# BSB-LAN-Full-Wifi.net
KiCad netlist of a schematic drawn in EAGLE
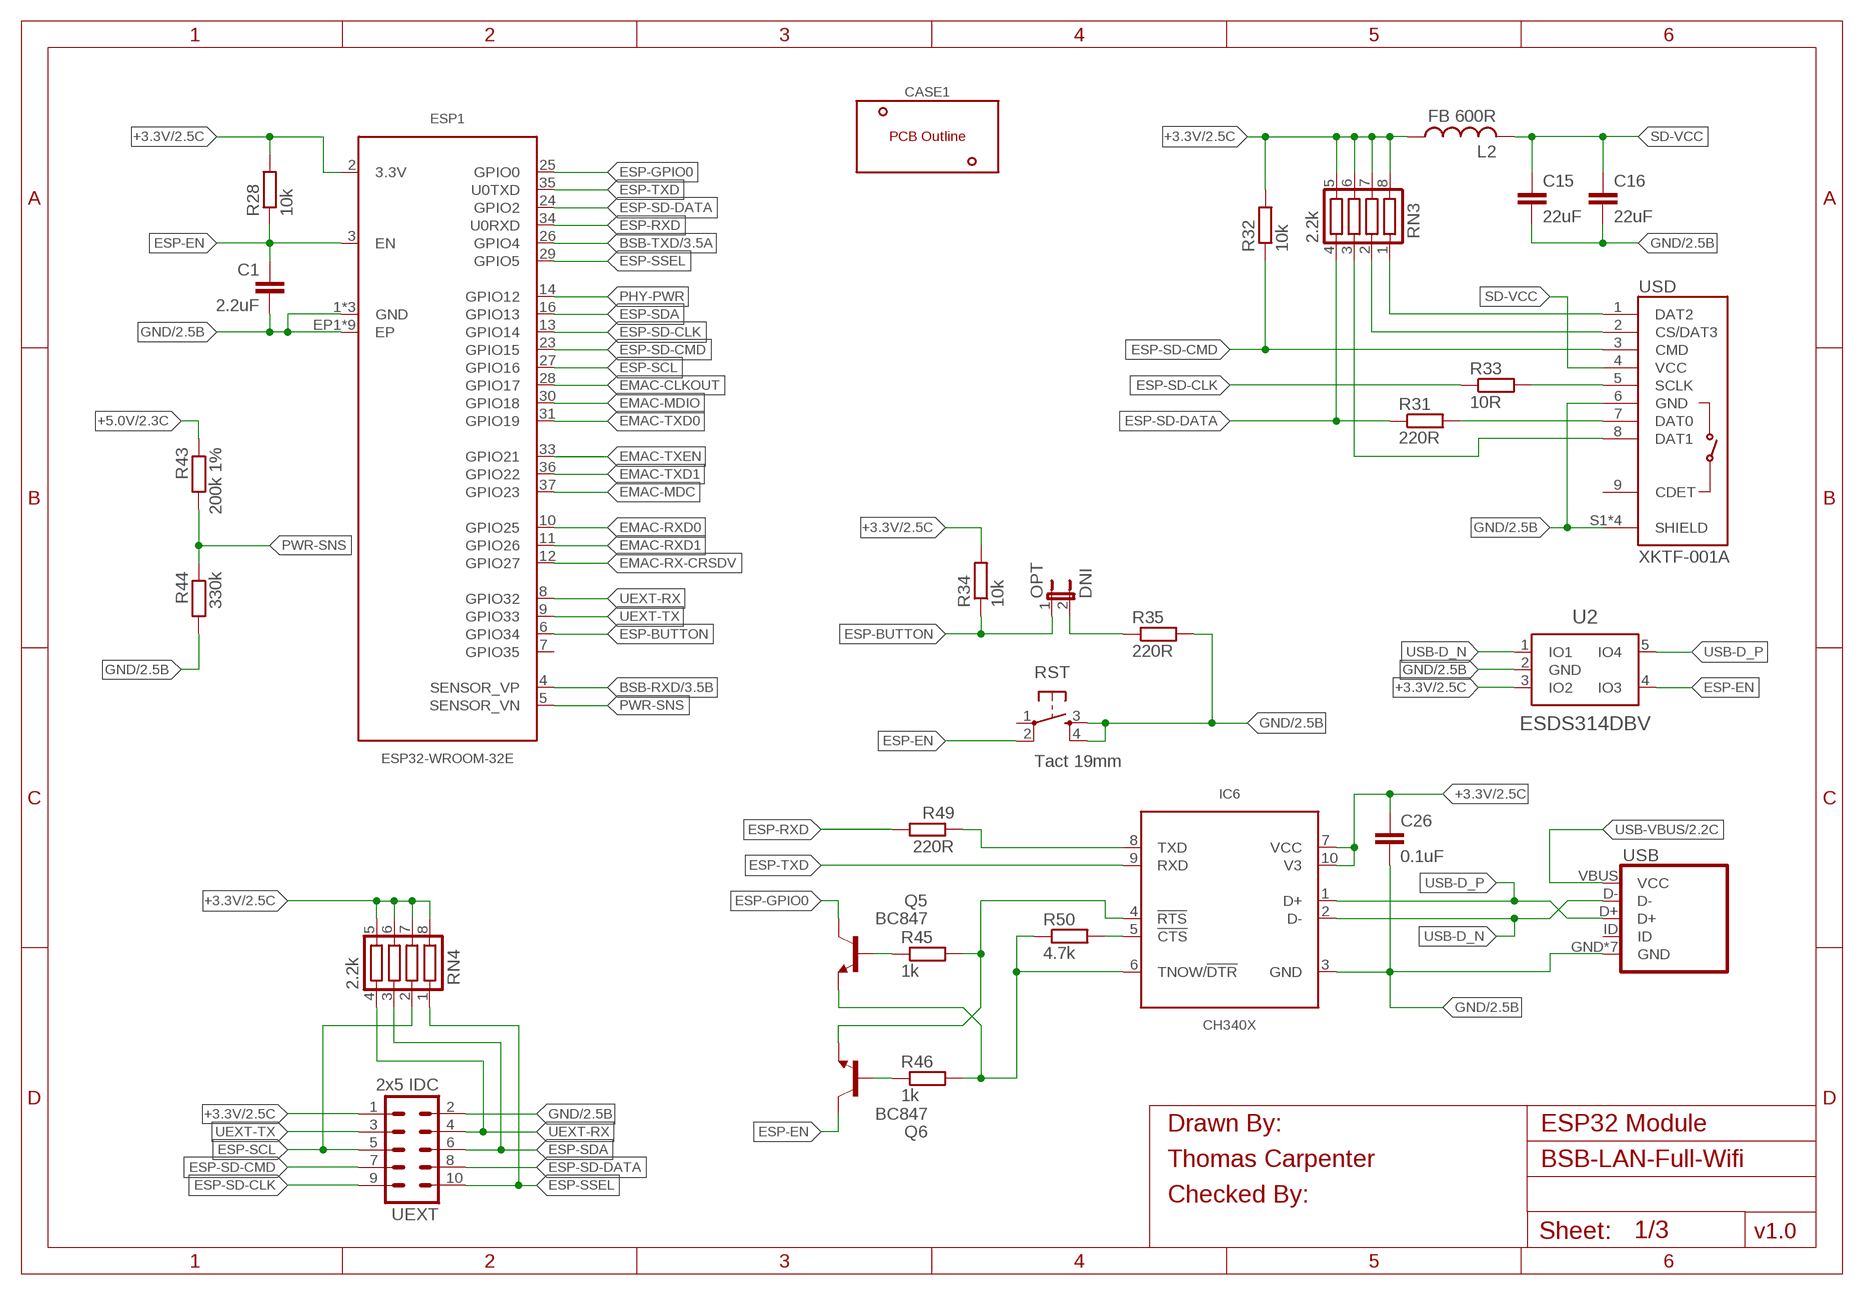
[diagram p0: schematic, sheet 1]
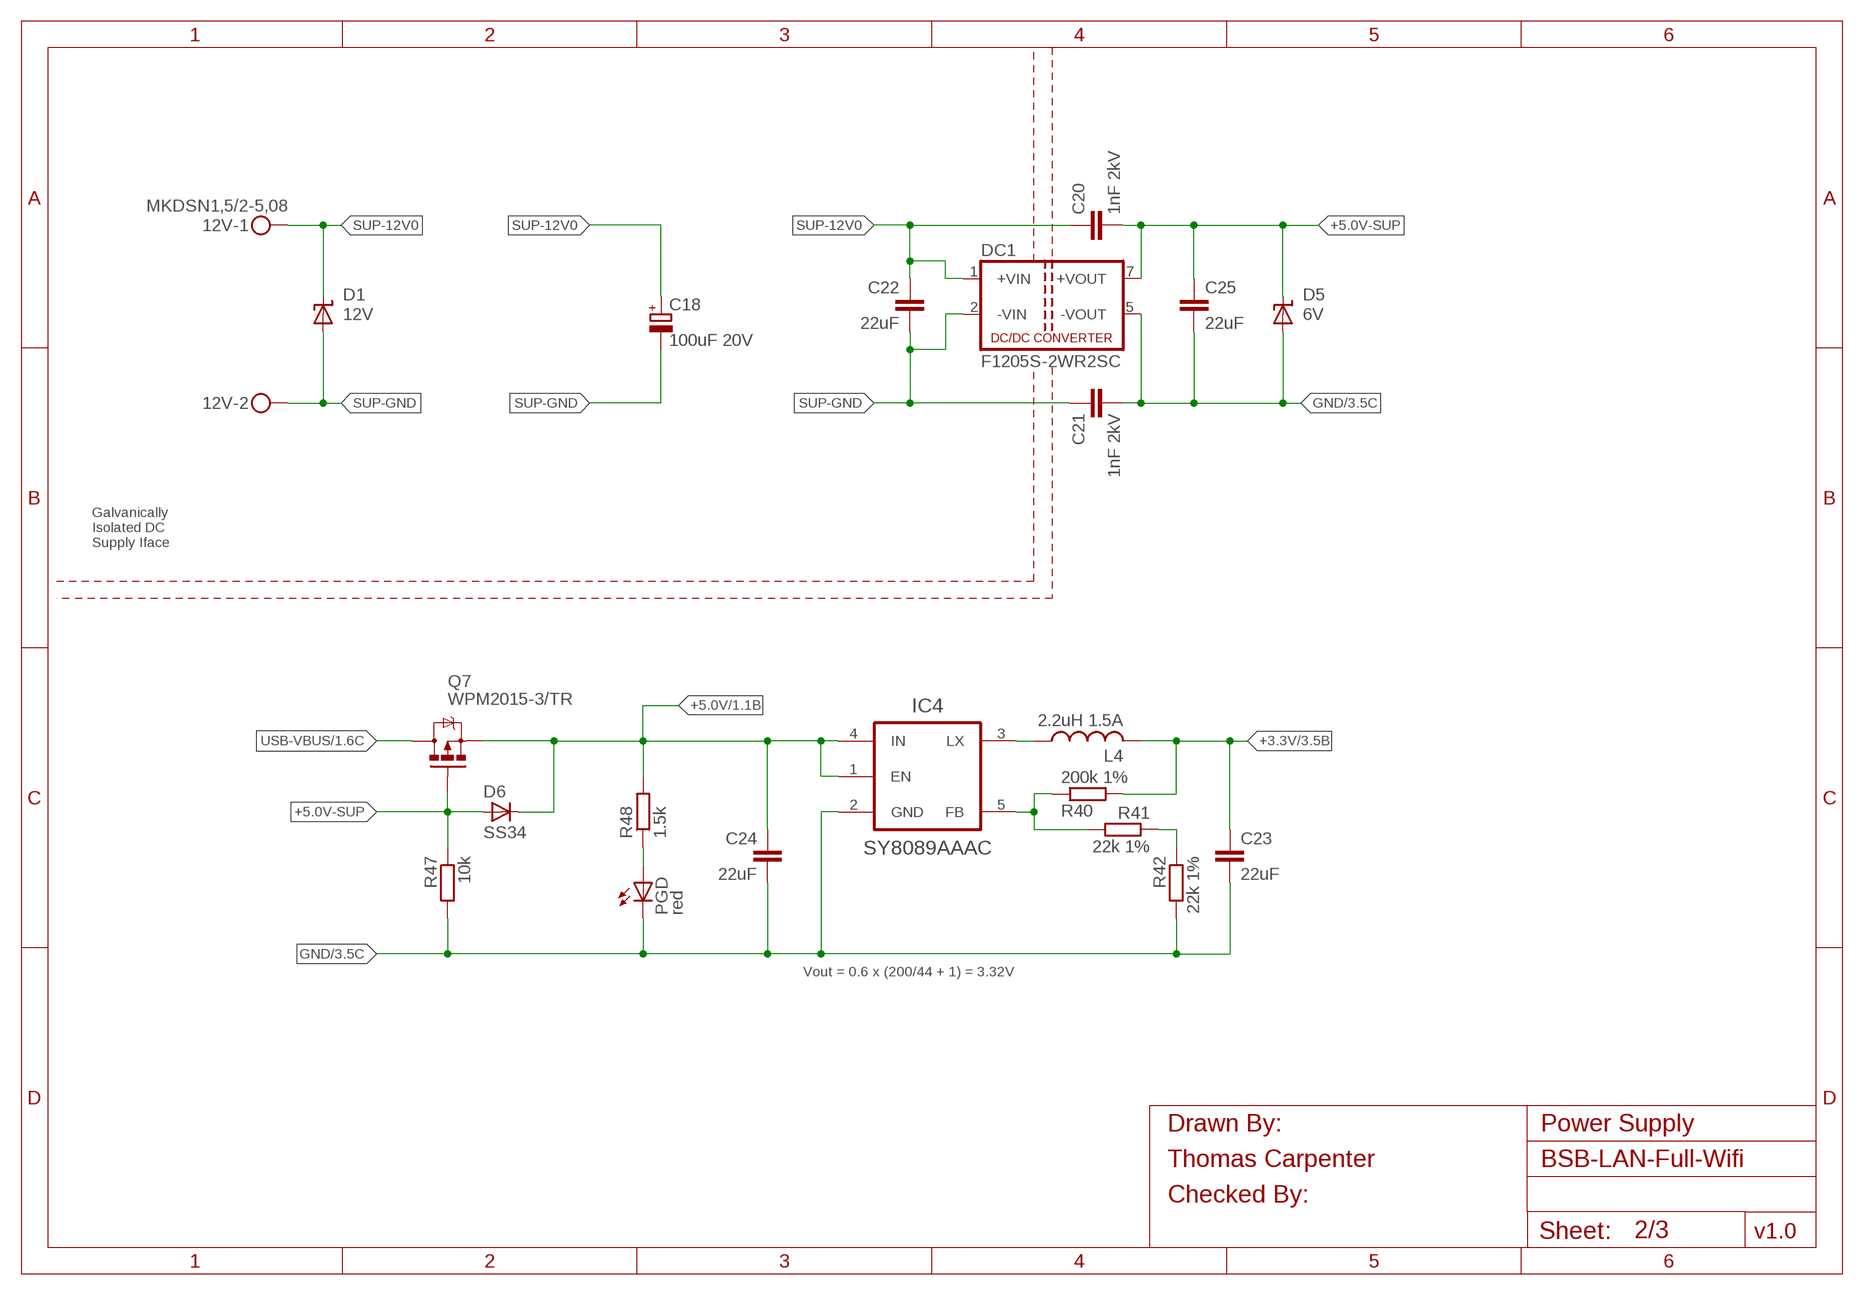
[diagram p1: schematic, sheet 2]
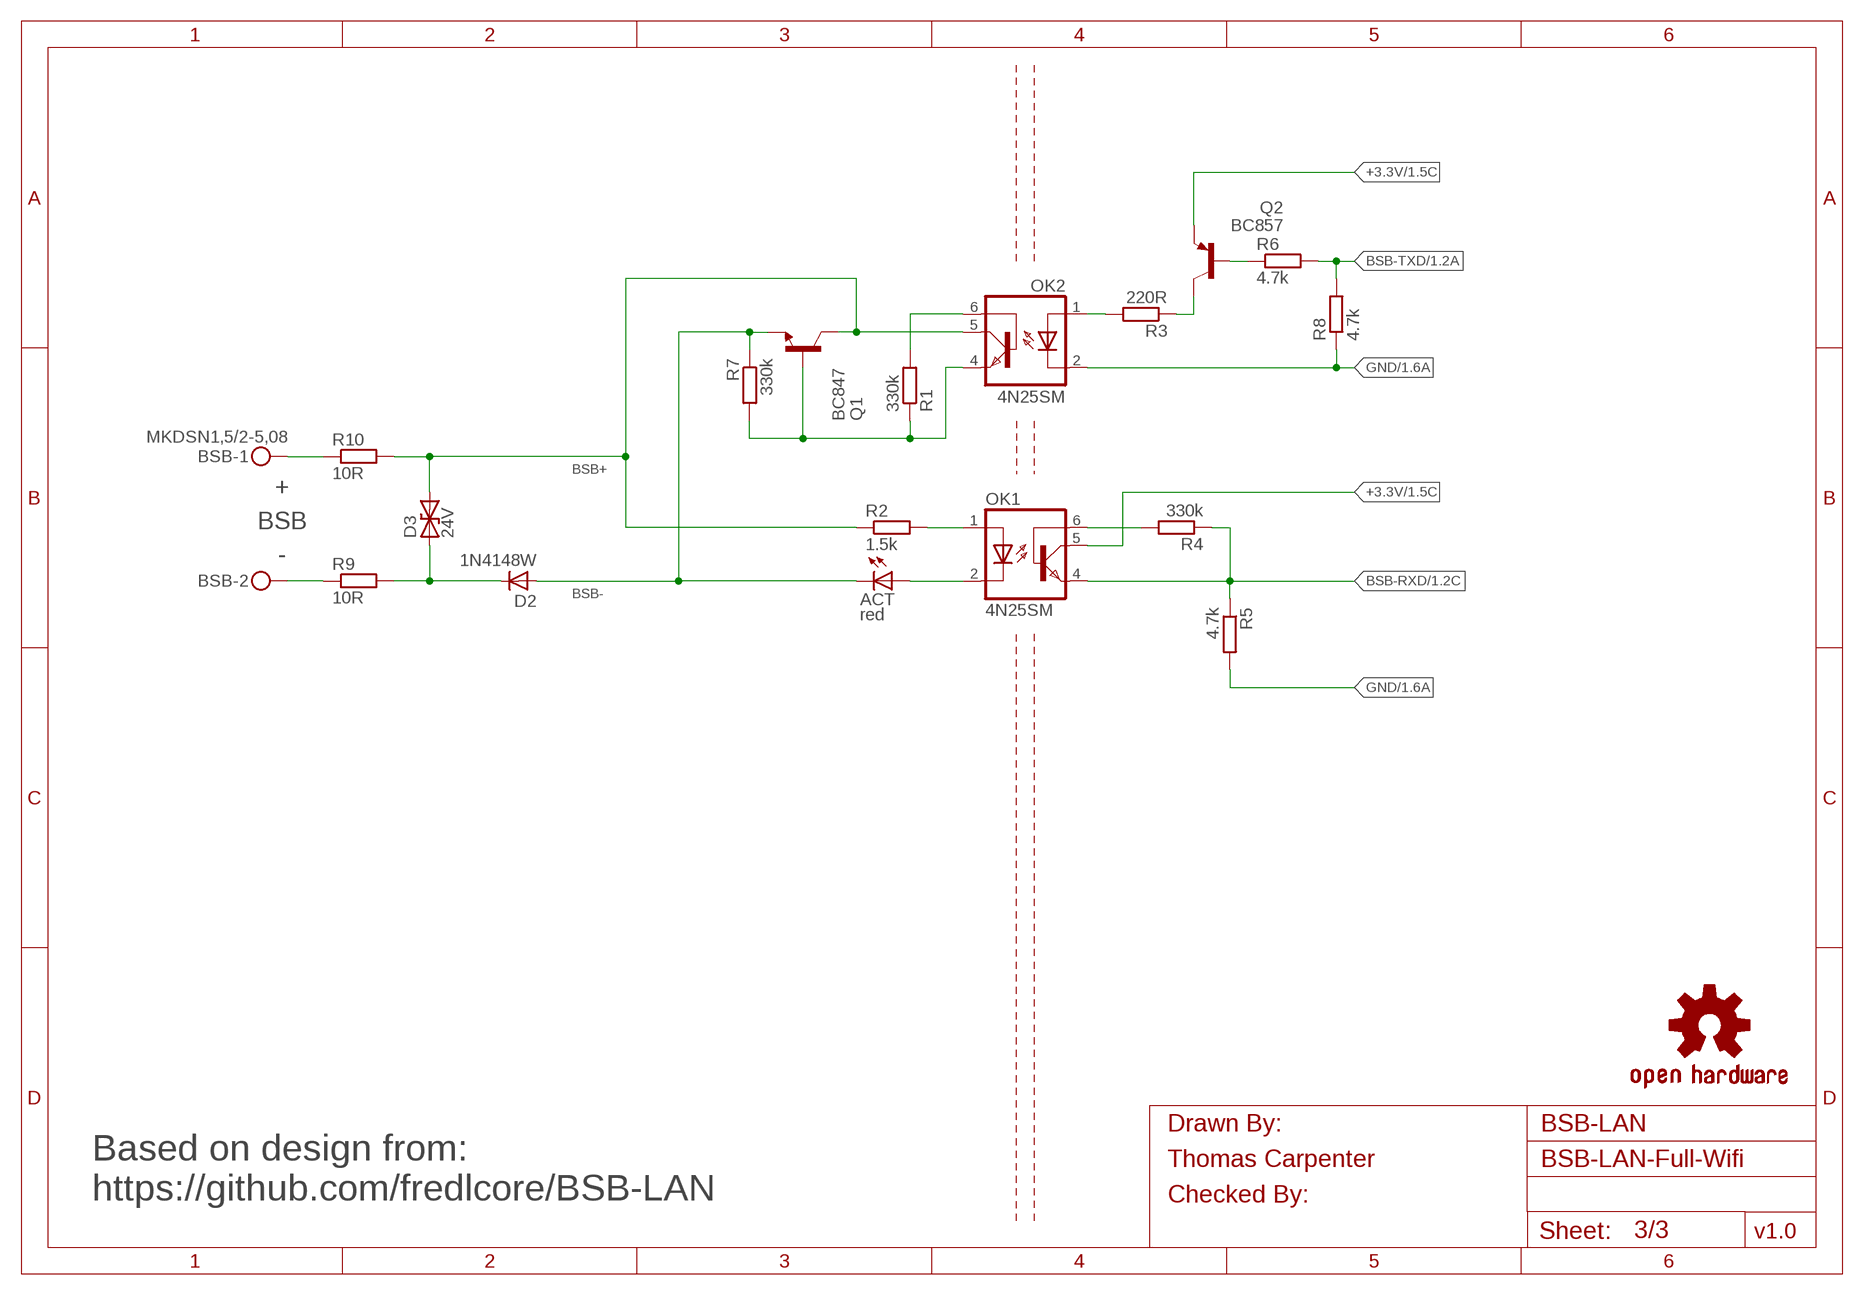
[diagram p2: schematic, sheet 3]

(export (version "E")
  (design (tool "Eeschema 10.0.6"))
  (components
    (comp (ref "12V")
      (value "MKDSN1,5/2-5,08")
      (footprint "eagle-import:MKDSN1_5-2-5_08")
      (fields (field (name "LCSC_PART") "C5183989"))
      (libsource (lib "eagle-import") (part "MKDSN1,5/2-5,08"))
    )
    (comp (ref "C18")
      (value "100uF 20V")
      (footprint "eagle-import:SMC_D")
      (fields (field (name "LCSC_PART") "C7224"))
      (libsource (lib "eagle-import") (part "CPOL-EUSMCD"))
    )
    (comp (ref "C20")
      (value "1nF 2kV")
      (footprint "eagle-import:C1206L")
      (fields (field (name "LCSC_PART") "C9196"))
      (libsource (lib "eagle-import") (part "C-EUC1206L"))
    )
    (comp (ref "C21")
      (value "1nF 2kV")
      (footprint "eagle-import:C1206L")
      (fields (field (name "LCSC_PART") "C9196"))
      (libsource (lib "eagle-import") (part "C-EUC1206L"))
    )
    (comp (ref "C22")
      (value "22uF")
      (footprint "eagle-import:C0805")
      (fields (field (name "LCSC_PART") "C45783"))
      (libsource (lib "eagle-import") (part "C-EUC0805"))
    )
    (comp (ref "C23")
      (value "22uF")
      (footprint "eagle-import:C0805")
      (fields (field (name "LCSC_PART") "C45783"))
      (libsource (lib "eagle-import") (part "C-EUC0805"))
    )
    (comp (ref "C24")
      (value "22uF")
      (footprint "eagle-import:C0805")
      (fields (field (name "LCSC_PART") "C45783"))
      (libsource (lib "eagle-import") (part "C-EUC0805"))
    )
    (comp (ref "C25")
      (value "22uF")
      (footprint "eagle-import:C0805")
      (fields (field (name "LCSC_PART") "C45783"))
      (libsource (lib "eagle-import") (part "C-EUC0805"))
    )
    (comp (ref "D1")
      (value "12V")
      (footprint "eagle-import:SMA")
      (fields (field (name "LCSC_PART") "C148213"))
      (libsource (lib "eagle-import") (part "TVS-UNISMA"))
    )
    (comp (ref "D5")
      (value "6V")
      (footprint "eagle-import:SMA")
      (fields (field (name "LCSC_PART") "C223993"))
      (libsource (lib "eagle-import") (part "TVS-UNISMA"))
    )
    (comp (ref "D6")
      (value "SS34")
      (footprint "eagle-import:SMA")
      (fields (field (name "LCSC_PART") "C8678"))
      (libsource (lib "eagle-import") (part "DIODE-SMA"))
    )
    (comp (ref "DC1")
      (value "F1205S-2WR2SC")
      (footprint "eagle-import:SIP7-N")
      (fields (field (name "LCSC_PART") "C5369565"))
      (libsource (lib "eagle-import") (part "FS-2WR2SC1205"))
    )
    (comp (ref "IC4")
      (value "SY8089AAAC")
      (footprint "eagle-import:DBV0005A-SOT23")
      (fields (field (name "LCSC_PART") "C78988"))
      (libsource (lib "eagle-import") (part "SY8089?CAAA"))
    )
    (comp (ref "L4")
      (value "2.2uH 1.5A")
      (footprint "eagle-import:L4040P")
      (fields (field (name "LCSC_PART") "C135262"))
      (libsource (lib "eagle-import") (part "L-USL4040P"))
    )
    (comp (ref "PGD")
      (value "red")
      (footprint "eagle-import:CHIP-LED0603")
      (fields (field (name "LCSC_PART") "C2286"))
      (libsource (lib "eagle-import") (part "LEDCHIPLED_0603"))
    )
    (comp (ref "Q7")
      (value "WPM2015-3/TR")
      (footprint "eagle-import:SOT23")
      (fields (field (name "LCSC_PART") "C7472861"))
      (libsource (lib "eagle-import") (part "WPM2015-3/TR"))
    )
    (comp (ref "R40")
      (value "200k 1%")
      (footprint "eagle-import:R0402")
      (fields (field (name "LCSC_PART") "C25764"))
      (libsource (lib "eagle-import") (part "R-EU_R0402"))
    )
    (comp (ref "R41")
      (value "22k 1%")
      (footprint "eagle-import:R0402")
      (fields (field (name "LCSC_PART") "C25768"))
      (libsource (lib "eagle-import") (part "R-EU_R0402"))
    )
    (comp (ref "R42")
      (value "22k 1%")
      (footprint "eagle-import:R0402")
      (fields (field (name "LCSC_PART") "C25768"))
      (libsource (lib "eagle-import") (part "R-EU_R0402"))
    )
    (comp (ref "R47")
      (value "10k")
      (footprint "eagle-import:R0402")
      (fields (field (name "LCSC_PART") "C25744"))
      (libsource (lib "eagle-import") (part "R-EU_R0402"))
    )
    (comp (ref "R48")
      (value "1.5k")
      (footprint "eagle-import:R0603")
      (fields (field (name "LCSC_PART") "C22843"))
      (libsource (lib "eagle-import") (part "R-EU_R0603"))
    )
    (comp (ref "C1")
      (value "2.2uF")
      (footprint "eagle-import:C0603")
      (fields (field (name "LCSC_PART") "C23630"))
      (libsource (lib "eagle-import") (part "C-EUC0603"))
    )
    (comp (ref "C15")
      (value "22uF")
      (footprint "eagle-import:C0805L")
      (fields (field (name "LCSC_PART") "C45783"))
      (libsource (lib "eagle-import") (part "C-EUC0805L"))
    )
    (comp (ref "C16")
      (value "22uF")
      (footprint "eagle-import:C0805L")
      (fields (field (name "LCSC_PART") "C45783"))
      (libsource (lib "eagle-import") (part "C-EUC0805L"))
    )
    (comp (ref "C26")
      (value "0.1uF")
      (footprint "eagle-import:C0402")
      (fields (field (name "LCSC_PART") "C1525"))
      (libsource (lib "eagle-import") (part "C-EUC0402"))
    )
    (comp (ref "CASE1")
      (value "DNI")
      (footprint "eagle-import:CNMB_2-")
      (libsource (lib "eagle-import") (part "CNMB/2"))
    )
    (comp (ref "ESP1")
      (value "ESP32-WROOM-32E")
      (footprint "eagle-import:ESP32-WROOM-32E")
      (fields (field (name "LCSC_PART") "C701341"))
      (libsource (lib "eagle-import") (part "ESP32-WROOM-32E"))
    )
    (comp (ref "IC6")
      (value "CH340X")
      (footprint "eagle-import:MSOP10")
      (fields (field (name "LCSC_PART") "C3035748"))
      (libsource (lib "eagle-import") (part "CH340X"))
    )
    (comp (ref "L2")
      (value "FB 600R")
      (footprint "eagle-import:L2010")
      (fields (field (name "LCSC_PART") "C1017"))
      (libsource (lib "eagle-import") (part "L-USL0805"))
    )
    (comp (ref "OPT")
      (value "DNI")
      (footprint "eagle-import:1X02")
      (libsource (lib "eagle-import") (part "JUMPER-2-PTH"))
    )
    (comp (ref "Q5")
      (value "BC847")
      (footprint "eagle-import:SOT23")
      (fields (field (name "LCSC_PART") "C130417") (field (name "LCSC_PART_1") "C130417"))
      (libsource (lib "eagle-import") (part "BC847"))
    )
    (comp (ref "Q6")
      (value "BC847")
      (footprint "eagle-import:SOT23")
      (fields (field (name "LCSC_PART") "C130417"))
      (libsource (lib "eagle-import") (part "BC847"))
    )
    (comp (ref "R28")
      (value "10k")
      (footprint "eagle-import:R0402")
      (fields (field (name "LCSC_PART") "C25744"))
      (libsource (lib "eagle-import") (part "R-EU_R0402"))
    )
    (comp (ref "R31")
      (value "220R")
      (footprint "eagle-import:R0402")
      (fields (field (name "LCSC_PART") "C25091"))
      (libsource (lib "eagle-import") (part "R-EU_R0402"))
    )
    (comp (ref "R32")
      (value "10k")
      (footprint "eagle-import:R0402")
      (fields (field (name "LCSC_PART") "C25744"))
      (libsource (lib "eagle-import") (part "R-EU_R0402"))
    )
    (comp (ref "R33")
      (value "10R")
      (footprint "eagle-import:R0603L")
      (fields (field (name "LCSC_PART") "C22859"))
      (libsource (lib "eagle-import") (part "R-EU_R0603L"))
    )
    (comp (ref "R34")
      (value "10k")
      (footprint "eagle-import:R0402")
      (fields (field (name "LCSC_PART") "C25744"))
      (libsource (lib "eagle-import") (part "R-EU_R0402"))
    )
    (comp (ref "R35")
      (value "220R")
      (footprint "eagle-import:R0402")
      (fields (field (name "LCSC_PART") "C25091"))
      (libsource (lib "eagle-import") (part "R-EU_R0402"))
    )
    (comp (ref "R43")
      (value "200k 1%")
      (footprint "eagle-import:R0402")
      (fields (field (name "LCSC_PART") "C25764"))
      (libsource (lib "eagle-import") (part "R-EU_R0402"))
    )
    (comp (ref "R44")
      (value "330k")
      (footprint "eagle-import:R0603L")
      (fields (field (name "LCSC_PART") "C23137"))
      (libsource (lib "eagle-import") (part "R-EU_R0603L"))
    )
    (comp (ref "R45")
      (value "1k")
      (footprint "eagle-import:R0402")
      (fields (field (name "LCSC_PART") "C11702"))
      (libsource (lib "eagle-import") (part "R-EU_R0402"))
    )
    (comp (ref "R46")
      (value "1k")
      (footprint "eagle-import:R0402")
      (fields (field (name "LCSC_PART") "C11702"))
      (libsource (lib "eagle-import") (part "R-EU_R0402"))
    )
    (comp (ref "R49")
      (value "220R")
      (footprint "eagle-import:R0402")
      (fields (field (name "LCSC_PART") "C25091"))
      (libsource (lib "eagle-import") (part "R-EU_R0402"))
    )
    (comp (ref "R50")
      (value "4.7k")
      (footprint "eagle-import:R0402")
      (fields (field (name "LCSC_PART") "C25900"))
      (libsource (lib "eagle-import") (part "R-EU_R0402"))
    )
    (comp (ref "RN3")
      (value "2.2k")
      (footprint "eagle-import:CTS742C083")
      (fields (field (name "LCSC_PART") "C414564"))
      (libsource (lib "eagle-import") (part "R-NET-04-R1206"))
    )
    (comp (ref "RN4")
      (value "2.2k")
      (footprint "eagle-import:CTS742C083")
      (fields (field (name "LCSC_PART") "C414564"))
      (libsource (lib "eagle-import") (part "R-NET-04-R1206"))
    )
    (comp (ref "RST")
      (value "Tact 19mm")
      (footprint "eagle-import:TACTILE_SWITCH")
      (fields (field (name "LCSC_PART") "C13828") (field (name "LCSC_PART_1") "C2837529"))
      (libsource (lib "eagle-import") (part "SWITCH-MOMENTARY"))
    )
    (comp (ref "U2")
      (value "ESDS314DBV")
      (footprint "eagle-import:DBV0005A-SOT23")
      (fields (field (name "LCSC_PART") "C1847859"))
      (libsource (lib "eagle-import") (part "ESDS314DBV"))
    )
    (comp (ref "UEXT")
      (value "2x5 IDC")
      (footprint "eagle-import:ML10")
      (fields (field (name "LCSC_PART") "C5665"))
      (libsource (lib "eagle-import") (part "ML10"))
    )
    (comp (ref "USB")
      (value "ZX62-B-5PA(33)")
      (footprint "eagle-import:USB-MICROB")
      (fields (field (name "LCSC_PART") "C132561"))
      (libsource (lib "eagle-import") (part "USB_MICROB_PLUG"))
    )
    (comp (ref "USD")
      (value "XKTF-001A")
      (footprint "eagle-import:MICRO-SD")
      (fields (field (name "LCSC_PART") "C381079"))
      (libsource (lib "eagle-import") (part "MICROSD"))
    )
    (comp (ref "ACT")
      (value "red")
      (footprint "eagle-import:CHIP-LED0603")
      (fields (field (name "LCSC_PART") "C2286"))
      (libsource (lib "eagle-import") (part "LEDCHIPLED_0603"))
    )
    (comp (ref "BSB")
      (value "MKDSN1,5/2-5,08")
      (footprint "eagle-import:MKDSN1_5-2-5_08")
      (fields (field (name "LCSC_PART") "C5183989"))
      (libsource (lib "eagle-import") (part "MKDSN1,5/2-5,08"))
    )
    (comp (ref "D2")
      (value "1N4148W")
      (footprint "eagle-import:SOD123")
      (fields (field (name "LCSC_PART") "C81598"))
      (libsource (lib "eagle-import") (part "DIODE-SOD123"))
    )
    (comp (ref "D3")
      (value "24V")
      (footprint "eagle-import:SMBG")
      (fields (field (name "LCSC_PART") "C83268"))
      (libsource (lib "eagle-import") (part "TVS-BIDIRSMB"))
    )
    (comp (ref "OK1")
      (value "4N25SM")
      (footprint "eagle-import:DIL6-SMD")
      (fields (field (name "LCSC_PART") "C258246") (field (name "LCSC_PART_1") "C258246"))
      (libsource (lib "eagle-import") (part "4N?MS25"))
    )
    (comp (ref "OK2")
      (value "4N25SM")
      (footprint "eagle-import:DIL6-SMD")
      (fields (field (name "LCSC_PART") "C258246") (field (name "LCSC_PART_1") "C258246"))
      (libsource (lib "eagle-import") (part "4N?MS25"))
    )
    (comp (ref "Q1")
      (value "BC847")
      (footprint "eagle-import:SOT23")
      (fields (field (name "LCSC_PART") "C130417") (field (name "LCSC_PART_1") "C130417"))
      (libsource (lib "eagle-import") (part "BC847"))
    )
    (comp (ref "Q2")
      (value "BC857")
      (footprint "eagle-import:SOT23-BEC")
      (fields (field (name "LCSC_PART") "C426782") (field (name "LCSC_PART_1") "C426782"))
      (libsource (lib "eagle-import") (part "BC857"))
    )
    (comp (ref "R1")
      (value "330k")
      (footprint "eagle-import:R0603")
      (fields (field (name "LCSC_PART") "C23137"))
      (libsource (lib "eagle-import") (part "R-EU_R0603"))
    )
    (comp (ref "R2")
      (value "1.5k")
      (footprint "eagle-import:R0603")
      (fields (field (name "LCSC_PART") "C22843"))
      (libsource (lib "eagle-import") (part "R-EU_R0603"))
    )
    (comp (ref "R3")
      (value "220R")
      (footprint "eagle-import:R0402")
      (fields (field (name "LCSC_PART") "C25091"))
      (libsource (lib "eagle-import") (part "R-EU_R0402"))
    )
    (comp (ref "R4")
      (value "330k")
      (footprint "eagle-import:R0603")
      (fields (field (name "LCSC_PART") "C23137"))
      (libsource (lib "eagle-import") (part "R-EU_R0603"))
    )
    (comp (ref "R5")
      (value "4.7k")
      (footprint "eagle-import:R0402")
      (fields (field (name "LCSC_PART") "C25900"))
      (libsource (lib "eagle-import") (part "R-EU_R0402"))
    )
    (comp (ref "R6")
      (value "4.7k")
      (footprint "eagle-import:R0402")
      (fields (field (name "LCSC_PART") "C25900"))
      (libsource (lib "eagle-import") (part "R-EU_R0402"))
    )
    (comp (ref "R7")
      (value "330k")
      (footprint "eagle-import:R0603")
      (fields (field (name "LCSC_PART") "C23137"))
      (libsource (lib "eagle-import") (part "R-EU_R0603"))
    )
    (comp (ref "R8")
      (value "4.7k")
      (footprint "eagle-import:R0402")
      (fields (field (name "LCSC_PART") "C25900"))
      (libsource (lib "eagle-import") (part "R-EU_R0402"))
    )
    (comp (ref "R9")
      (value "10R")
      (footprint "eagle-import:R0603")
      (fields (field (name "LCSC_PART") "C22859"))
      (libsource (lib "eagle-import") (part "R-EU_R0603"))
    )
    (comp (ref "R10")
      (value "10R")
      (footprint "eagle-import:R0603")
      (fields (field (name "LCSC_PART") "C22859"))
      (libsource (lib "eagle-import") (part "R-EU_R0603"))
    )
    (comp (ref "U$3")
      (value "DNI")
      (footprint "eagle-import:OSHW-LOGO-M")
      (libsource (lib "eagle-import") (part "OSHW-LOGOM"))
    )
  )
  (nets
    (net (code "1") (name "+3.3V") (class "Default")
      (node (ref "C23") (pin "1") (pinfunction "1_1") (pintype "passive"))
      (node (ref "C26") (pin "1") (pinfunction "1_1") (pintype "passive"))
      (node (ref "ESP1") (pin "2") (pinfunction "3.3V_2") (pintype "power_in"))
      (node (ref "IC6") (pin "10") (pinfunction "V3_10") (pintype "power_in"))
      (node (ref "IC6") (pin "7") (pinfunction "VCC_7") (pintype "power_in"))
      (node (ref "L2") (pin "1") (pinfunction "1_1") (pintype "passive"))
      (node (ref "L4") (pin "2") (pinfunction "2_2") (pintype "passive"))
      (node (ref "OK1") (pin "5") (pinfunction "COL_5") (pintype "passive"))
      (node (ref "Q2") (pin "E") (pinfunction "E_E") (pintype "passive"))
      (node (ref "R28") (pin "2") (pinfunction "2_2") (pintype "passive"))
      (node (ref "R32") (pin "2") (pinfunction "2_2") (pintype "passive"))
      (node (ref "R34") (pin "2") (pinfunction "2_2") (pintype "passive"))
      (node (ref "R40") (pin "2") (pinfunction "2_2") (pintype "passive"))
      (node (ref "RN3") (pin "5") (pinfunction "5_5") (pintype "passive"))
      (node (ref "RN3") (pin "6") (pinfunction "6_6") (pintype "passive"))
      (node (ref "RN3") (pin "7") (pinfunction "7_7") (pintype "passive"))
      (node (ref "RN3") (pin "8") (pinfunction "8_8") (pintype "passive"))
      (node (ref "RN4") (pin "5") (pinfunction "5_5") (pintype "passive"))
      (node (ref "RN4") (pin "6") (pinfunction "6_6") (pintype "passive"))
      (node (ref "RN4") (pin "7") (pinfunction "7_7") (pintype "passive"))
      (node (ref "RN4") (pin "8") (pinfunction "8_8") (pintype "passive"))
      (node (ref "U2") (pin "3") (pinfunction "IO2_3") (pintype "passive"))
      (node (ref "UEXT") (pin "1") (pinfunction "1_1") (pintype "passive"))
    )
    (net (code "2") (name "+5.0V") (class "Default")
      (node (ref "C24") (pin "1") (pinfunction "1_1") (pintype "passive"))
      (node (ref "D6") (pin "C") (pinfunction "C_C") (pintype "passive"))
      (node (ref "IC4") (pin "1") (pinfunction "EN_1") (pintype "input"))
      (node (ref "IC4") (pin "4") (pinfunction "IN_4") (pintype "power_in"))
      (node (ref "Q7") (pin "2") (pinfunction "S_2") (pintype "passive"))
      (node (ref "R43") (pin "1") (pinfunction "1_1") (pintype "passive"))
      (node (ref "R48") (pin "2") (pinfunction "2_2") (pintype "passive"))
    )
    (net (code "3") (name "+5.0V-SUP") (class "Default")
      (node (ref "C20") (pin "2") (pinfunction "2_2") (pintype "passive"))
      (node (ref "C25") (pin "1") (pinfunction "1_1") (pintype "passive"))
      (node (ref "D5") (pin "C") (pinfunction "C_C") (pintype "passive"))
      (node (ref "D6") (pin "A") (pinfunction "A_A") (pintype "passive"))
      (node (ref "DC1") (pin "7") (pinfunction "+VOUT_7") (pintype "passive"))
      (node (ref "Q7") (pin "1") (pinfunction "G_1") (pintype "passive"))
      (node (ref "R47") (pin "1") (pinfunction "1_1") (pintype "passive"))
    )
    (net (code "4") (name "BSB+") (class "Default")
      (node (ref "D3") (pin "2") (pinfunction "2_2") (pintype "passive"))
      (node (ref "OK2") (pin "5") (pinfunction "COL_5") (pintype "passive"))
      (node (ref "Q1") (pin "3") (pinfunction "C_3") (pintype "passive"))
      (node (ref "R10") (pin "2") (pinfunction "2_2") (pintype "passive"))
      (node (ref "R2") (pin "1") (pinfunction "1_1") (pintype "passive"))
    )
    (net (code "5") (name "BSB-") (class "Default")
      (node (ref "ACT") (pin "C") (pinfunction "C_C") (pintype "passive"))
      (node (ref "D2") (pin "A") (pinfunction "A_A") (pintype "passive"))
      (node (ref "Q1") (pin "2") (pinfunction "E_2") (pintype "passive"))
      (node (ref "R7") (pin "1") (pinfunction "1_1") (pintype "passive"))
    )
    (net (code "6") (name "BSB-RXD") (class "Default")
      (node (ref "ESP1") (pin "4") (pinfunction "SENSOR_VP_4") (pintype "bidirectional"))
      (node (ref "OK1") (pin "4") (pinfunction "EMI_4") (pintype "passive"))
      (node (ref "R4") (pin "1") (pinfunction "1_1") (pintype "passive"))
      (node (ref "R5") (pin "1") (pinfunction "1_1") (pintype "passive"))
    )
    (net (code "7") (name "BSB-TXD") (class "Default")
      (node (ref "ESP1") (pin "26") (pinfunction "GPIO4_26") (pintype "bidirectional"))
      (node (ref "R6") (pin "2") (pinfunction "2_2") (pintype "passive"))
      (node (ref "R8") (pin "2") (pinfunction "2_2") (pintype "passive"))
    )
    (net (code "8") (name "EMAC-CLKOUT") (class "Default")
      (node (ref "ESP1") (pin "28") (pinfunction "GPIO17_28") (pintype "bidirectional"))
    )
    (net (code "9") (name "EMAC-MDC") (class "Default")
      (node (ref "ESP1") (pin "37") (pinfunction "GPIO23_37") (pintype "bidirectional"))
    )
    (net (code "10") (name "EMAC-MDIO") (class "Default")
      (node (ref "ESP1") (pin "30") (pinfunction "GPIO18_30") (pintype "bidirectional"))
    )
    (net (code "11") (name "EMAC-RX-CRSDV") (class "Default")
      (node (ref "ESP1") (pin "12") (pinfunction "GPIO27_12") (pintype "bidirectional"))
    )
    (net (code "12") (name "EMAC-RXD0") (class "Default")
      (node (ref "ESP1") (pin "10") (pinfunction "GPIO25_10") (pintype "bidirectional"))
    )
    (net (code "13") (name "EMAC-RXD1") (class "Default")
      (node (ref "ESP1") (pin "11") (pinfunction "GPIO26_11") (pintype "bidirectional"))
    )
    (net (code "14") (name "EMAC-TXD0") (class "Default")
      (node (ref "ESP1") (pin "31") (pinfunction "GPIO19_31") (pintype "bidirectional"))
    )
    (net (code "15") (name "EMAC-TXD1") (class "Default")
      (node (ref "ESP1") (pin "36") (pinfunction "GPIO22_36") (pintype "bidirectional"))
    )
    (net (code "16") (name "EMAC-TXEN") (class "Default")
      (node (ref "ESP1") (pin "33") (pinfunction "GPIO21_33") (pintype "bidirectional"))
    )
    (net (code "17") (name "ESP-BUTTON") (class "Default")
      (node (ref "ESP1") (pin "6") (pinfunction "GPIO34_6") (pintype "bidirectional"))
      (node (ref "OPT") (pin "1") (pinfunction "1_1") (pintype "passive"))
      (node (ref "R34") (pin "1") (pinfunction "1_1") (pintype "passive"))
    )
    (net (code "18") (name "ESP-EN") (class "Default")
      (node (ref "C1") (pin "1") (pinfunction "1_1") (pintype "passive"))
      (node (ref "ESP1") (pin "3") (pinfunction "EN_3") (pintype "input"))
      (node (ref "Q6") (pin "3") (pinfunction "C_3") (pintype "passive"))
      (node (ref "R28") (pin "1") (pinfunction "1_1") (pintype "passive"))
      (node (ref "RST") (pin "2") (pinfunction "2_2") (pintype "passive"))
      (node (ref "U2") (pin "4") (pinfunction "IO3_4") (pintype "passive"))
    )
    (net (code "19") (name "ESP-GPIO0") (class "Default")
      (node (ref "ESP1") (pin "25") (pinfunction "GPIO0_25") (pintype "bidirectional"))
      (node (ref "Q5") (pin "3") (pinfunction "C_3") (pintype "passive"))
    )
    (net (code "20") (name "ESP-RXD") (class "Default")
      (node (ref "ESP1") (pin "34") (pinfunction "U0RXD_34") (pintype "bidirectional"))
      (node (ref "R49") (pin "2") (pinfunction "2_2") (pintype "passive"))
    )
    (net (code "21") (name "ESP-SCL") (class "Default")
      (node (ref "ESP1") (pin "27") (pinfunction "GPIO16_27") (pintype "bidirectional"))
      (node (ref "RN4") (pin "2") (pinfunction "2_2") (pintype "passive"))
      (node (ref "UEXT") (pin "5") (pinfunction "5_5") (pintype "passive"))
    )
    (net (code "22") (name "ESP-SD-CLK") (class "Default")
      (node (ref "ESP1") (pin "13") (pinfunction "GPIO14_13") (pintype "bidirectional"))
      (node (ref "R33") (pin "1") (pinfunction "1_1") (pintype "passive"))
      (node (ref "UEXT") (pin "9") (pinfunction "9_9") (pintype "passive"))
    )
    (net (code "23") (name "ESP-SD-CMD") (class "Default")
      (node (ref "ESP1") (pin "23") (pinfunction "GPIO15_23") (pintype "bidirectional"))
      (node (ref "R32") (pin "1") (pinfunction "1_1") (pintype "passive"))
      (node (ref "UEXT") (pin "7") (pinfunction "7_7") (pintype "passive"))
      (node (ref "USD") (pin "3") (pinfunction "CMD_3") (pintype "bidirectional"))
    )
    (net (code "24") (name "ESP-SD-DATA") (class "Default")
      (node (ref "ESP1") (pin "24") (pinfunction "GPIO2_24") (pintype "bidirectional"))
      (node (ref "R31") (pin "1") (pinfunction "1_1") (pintype "passive"))
      (node (ref "RN3") (pin "4") (pinfunction "4_4") (pintype "passive"))
      (node (ref "UEXT") (pin "8") (pinfunction "8_8") (pintype "passive"))
    )
    (net (code "25") (name "ESP-SDA") (class "Default")
      (node (ref "ESP1") (pin "16") (pinfunction "GPIO13_16") (pintype "bidirectional"))
      (node (ref "RN4") (pin "3") (pinfunction "3_3") (pintype "passive"))
      (node (ref "UEXT") (pin "6") (pinfunction "6_6") (pintype "passive"))
    )
    (net (code "26") (name "ESP-SSEL") (class "Default")
      (node (ref "ESP1") (pin "29") (pinfunction "GPIO5_29") (pintype "bidirectional"))
      (node (ref "RN4") (pin "1") (pinfunction "1_1") (pintype "passive"))
      (node (ref "UEXT") (pin "10") (pinfunction "10_10") (pintype "passive"))
    )
    (net (code "27") (name "ESP-TXD") (class "Default")
      (node (ref "ESP1") (pin "35") (pinfunction "U0TXD_35") (pintype "bidirectional"))
      (node (ref "IC6") (pin "9") (pinfunction "RXD_9") (pintype "input"))
    )
    (net (code "28") (name "GND") (class "Default")
      (node (ref "C1") (pin "2") (pinfunction "2_2") (pintype "passive"))
      (node (ref "C15") (pin "2") (pinfunction "2_2") (pintype "passive"))
      (node (ref "C16") (pin "2") (pinfunction "2_2") (pintype "passive"))
      (node (ref "C21") (pin "2") (pinfunction "2_2") (pintype "passive"))
      (node (ref "C23") (pin "2") (pinfunction "2_2") (pintype "passive"))
      (node (ref "C24") (pin "2") (pinfunction "2_2") (pintype "passive"))
      (node (ref "C25") (pin "2") (pinfunction "2_2") (pintype "passive"))
      (node (ref "C26") (pin "2") (pinfunction "2_2") (pintype "passive"))
      (node (ref "D5") (pin "A") (pinfunction "A_A") (pintype "passive"))
      (node (ref "DC1") (pin "5") (pinfunction "-VOUT_5") (pintype "passive"))
      (node (ref "ESP1") (pin "1") (pinfunction "GND_1") (pintype "power_in"))
      (node (ref "ESP1") (pin "15") (pinfunction "GND_15") (pintype "power_in"))
      (node (ref "ESP1") (pin "38") (pinfunction "GND_38") (pintype "power_in"))
      (node (ref "ESP1") (pin "EP1") (pinfunction "EP_EP1") (pintype "passive"))
      (node (ref "ESP1") (pin "EP2") (pinfunction "EP_EP2") (pintype "passive"))
      (node (ref "ESP1") (pin "EP3") (pinfunction "EP_EP3") (pintype "passive"))
      (node (ref "ESP1") (pin "EP4") (pinfunction "EP_EP4") (pintype "passive"))
      (node (ref "ESP1") (pin "EP5") (pinfunction "EP_EP5") (pintype "passive"))
      (node (ref "ESP1") (pin "EP6") (pinfunction "EP_EP6") (pintype "passive"))
      (node (ref "ESP1") (pin "EP7") (pinfunction "EP_EP7") (pintype "passive"))
      (node (ref "ESP1") (pin "EP8") (pinfunction "EP_EP8") (pintype "passive"))
      (node (ref "ESP1") (pin "EP9") (pinfunction "EP_EP9") (pintype "passive"))
      (node (ref "IC4") (pin "2") (pinfunction "GND_2") (pintype "power_in"))
      (node (ref "IC6") (pin "3") (pinfunction "GND_3") (pintype "power_in"))
      (node (ref "OK2") (pin "2") (pinfunction "C_2") (pintype "passive"))
      (node (ref "PGD") (pin "C") (pinfunction "C_C") (pintype "passive"))
      (node (ref "R35") (pin "2") (pinfunction "2_2") (pintype "passive"))
      (node (ref "R42") (pin "2") (pinfunction "2_2") (pintype "passive"))
      (node (ref "R44") (pin "2") (pinfunction "2_2") (pintype "passive"))
      (node (ref "R47") (pin "2") (pinfunction "2_2") (pintype "passive"))
      (node (ref "R5") (pin "2") (pinfunction "2_2") (pintype "passive"))
      (node (ref "R8") (pin "1") (pinfunction "1_1") (pintype "passive"))
      (node (ref "RST") (pin "3") (pinfunction "3_3") (pintype "passive"))
      (node (ref "RST") (pin "4") (pinfunction "4_4") (pintype "passive"))
      (node (ref "U2") (pin "2") (pinfunction "GND_2") (pintype "power_in"))
      (node (ref "UEXT") (pin "2") (pinfunction "2_2") (pintype "passive"))
      (node (ref "USB") (pin "GND") (pinfunction "GND_GND") (pintype "bidirectional"))
      (node (ref "USB") (pin "MT1") (pinfunction "GND_MT1") (pintype "bidirectional"))
      (node (ref "USB") (pin "MT2") (pinfunction "GND_MT2") (pintype "bidirectional"))
      (node (ref "USB") (pin "MT3") (pinfunction "GND_MT3") (pintype "bidirectional"))
      (node (ref "USB") (pin "MT4") (pinfunction "GND_MT4") (pintype "bidirectional"))
      (node (ref "USB") (pin "MT5") (pinfunction "GND_MT5") (pintype "bidirectional"))
      (node (ref "USB") (pin "MT6") (pinfunction "GND_MT6") (pintype "bidirectional"))
      (node (ref "USD") (pin "6") (pinfunction "GND_6") (pintype "power_in"))
      (node (ref "USD") (pin "S1") (pinfunction "SHIELD_S1") (pintype "passive"))
      (node (ref "USD") (pin "S2") (pinfunction "SHIELD_S2") (pintype "passive"))
      (node (ref "USD") (pin "S3") (pinfunction "SHIELD_S3") (pintype "passive"))
      (node (ref "USD") (pin "S4") (pinfunction "SHIELD_S4") (pintype "passive"))
    )
    (net (code "29") (name "Net-(BSB-Pad1)") (class "Default")
      (node (ref "BSB") (pin "1") (pinfunction "1_1") (pintype "passive"))
      (node (ref "R10") (pin "1") (pinfunction "1_1") (pintype "passive"))
    )
    (net (code "30") (name "Net-(BSBB-1)") (class "Default")
      (node (ref "BSB") (pin "2") (pinfunction "1_2") (pintype "passive"))
      (node (ref "R9") (pin "1") (pinfunction "1_1") (pintype "passive"))
    )
    (net (code "31") (name "Net-(D2-PadC)") (class "Default")
      (node (ref "D2") (pin "C") (pinfunction "C_C") (pintype "passive"))
      (node (ref "D3") (pin "1") (pinfunction "1_1") (pintype "passive"))
      (node (ref "R9") (pin "2") (pinfunction "2_2") (pintype "passive"))
    )
    (net (code "32") (name "Net-(IC4-FB)") (class "Default")
      (node (ref "IC4") (pin "5") (pinfunction "FB_5") (pintype "input"))
      (node (ref "R40") (pin "1") (pinfunction "1_1") (pintype "passive"))
      (node (ref "R41") (pin "2") (pinfunction "2_2") (pintype "passive"))
    )
    (net (code "33") (name "Net-(IC4-LX)") (class "Default")
      (node (ref "IC4") (pin "3") (pinfunction "LX_3") (pintype "output"))
      (node (ref "L4") (pin "1") (pinfunction "1_1") (pintype "passive"))
    )
    (net (code "34") (name "Net-(IC6-TNOW{slash}~{DTR})") (class "Default")
      (node (ref "IC6") (pin "6") (pinfunction "TNOW/~{DTR}_6") (pintype "bidirectional"))
      (node (ref "Q5") (pin "2") (pinfunction "E_2") (pintype "passive"))
      (node (ref "R46") (pin "2") (pinfunction "2_2") (pintype "passive"))
      (node (ref "R50") (pin "1") (pinfunction "1_1") (pintype "passive"))
    )
    (net (code "35") (name "Net-(IC6-TXD)") (class "Default")
      (node (ref "IC6") (pin "8") (pinfunction "TXD_8") (pintype "output"))
      (node (ref "R49") (pin "1") (pinfunction "1_1") (pintype "passive"))
    )
    (net (code "36") (name "Net-(IC6-~{CTS})") (class "Default")
      (node (ref "IC6") (pin "5") (pinfunction "~{CTS}_5") (pintype "input"))
      (node (ref "R50") (pin "2") (pinfunction "2_2") (pintype "passive"))
    )
    (net (code "37") (name "Net-(IC6-~{RTS})") (class "Default")
      (node (ref "IC6") (pin "4") (pinfunction "~{RTS}_4") (pintype "output"))
      (node (ref "Q6") (pin "2") (pinfunction "E_2") (pintype "passive"))
      (node (ref "R45") (pin "2") (pinfunction "2_2") (pintype "passive"))
    )
    (net (code "38") (name "Net-(OK1-A)") (class "Default")
      (node (ref "OK1") (pin "1") (pinfunction "A_1") (pintype "passive"))
      (node (ref "R2") (pin "2") (pinfunction "2_2") (pintype "passive"))
    )
    (net (code "39") (name "Net-(OK1-BAS)") (class "Default")
      (node (ref "OK1") (pin "6") (pinfunction "BAS_6") (pintype "passive"))
      (node (ref "R4") (pin "2") (pinfunction "2_2") (pintype "passive"))
    )
    (net (code "40") (name "Net-(OK1-C)") (class "Default")
      (node (ref "ACT") (pin "A") (pinfunction "A_A") (pintype "passive"))
      (node (ref "OK1") (pin "2") (pinfunction "C_2") (pintype "passive"))
    )
    (net (code "41") (name "Net-(OK2-A)") (class "Default")
      (node (ref "OK2") (pin "1") (pinfunction "A_1") (pintype "passive"))
      (node (ref "R3") (pin "2") (pinfunction "2_2") (pintype "passive"))
    )
    (net (code "42") (name "Net-(OK2-BAS)") (class "Default")
      (node (ref "OK2") (pin "6") (pinfunction "BAS_6") (pintype "passive"))
      (node (ref "R1") (pin "2") (pinfunction "2_2") (pintype "passive"))
    )
    (net (code "43") (name "Net-(OK2-EMI)") (class "Default")
      (node (ref "OK2") (pin "4") (pinfunction "EMI_4") (pintype "passive"))
      (node (ref "Q1") (pin "1") (pinfunction "B_1") (pintype "passive"))
      (node (ref "R1") (pin "1") (pinfunction "1_1") (pintype "passive"))
      (node (ref "R7") (pin "2") (pinfunction "2_2") (pintype "passive"))
    )
    (net (code "44") (name "Net-(OPT-Pad2)") (class "Default")
      (node (ref "OPT") (pin "2") (pinfunction "2_2") (pintype "passive"))
      (node (ref "R35") (pin "1") (pinfunction "1_1") (pintype "passive"))
    )
    (net (code "45") (name "Net-(PGD-PadA)") (class "Default")
      (node (ref "PGD") (pin "A") (pinfunction "A_A") (pintype "passive"))
      (node (ref "R48") (pin "1") (pinfunction "1_1") (pintype "passive"))
    )
    (net (code "46") (name "Net-(Q2-PadB)") (class "Default")
      (node (ref "Q2") (pin "B") (pinfunction "B_B") (pintype "passive"))
      (node (ref "R6") (pin "1") (pinfunction "1_1") (pintype "passive"))
    )
    (net (code "47") (name "Net-(Q2-PadC)") (class "Default")
      (node (ref "Q2") (pin "C") (pinfunction "C_C") (pintype "passive"))
      (node (ref "R3") (pin "1") (pinfunction "1_1") (pintype "passive"))
    )
    (net (code "48") (name "Net-(Q5-B)") (class "Default")
      (node (ref "Q5") (pin "1") (pinfunction "B_1") (pintype "passive"))
      (node (ref "R45") (pin "1") (pinfunction "1_1") (pintype "passive"))
    )
    (net (code "49") (name "Net-(Q6-B)") (class "Default")
      (node (ref "Q6") (pin "1") (pinfunction "B_1") (pintype "passive"))
      (node (ref "R46") (pin "1") (pinfunction "1_1") (pintype "passive"))
    )
    (net (code "50") (name "Net-(R41-Pad1)") (class "Default")
      (node (ref "R41") (pin "1") (pinfunction "1_1") (pintype "passive"))
      (node (ref "R42") (pin "1") (pinfunction "1_1") (pintype "passive"))
    )
    (net (code "51") (name "Net-(USD-CS{slash}DAT3)") (class "Default")
      (node (ref "RN3") (pin "2") (pinfunction "2_2") (pintype "passive"))
      (node (ref "USD") (pin "2") (pinfunction "CS/DAT3_2") (pintype "bidirectional"))
    )
    (net (code "52") (name "Net-(USD-DAT0)") (class "Default")
      (node (ref "R31") (pin "2") (pinfunction "2_2") (pintype "passive"))
      (node (ref "USD") (pin "7") (pinfunction "DAT0_7") (pintype "bidirectional"))
    )
    (net (code "53") (name "Net-(USD-DAT1)") (class "Default")
      (node (ref "RN3") (pin "3") (pinfunction "3_3") (pintype "passive"))
      (node (ref "USD") (pin "8") (pinfunction "DAT1_8") (pintype "bidirectional"))
    )
    (net (code "54") (name "Net-(USD-DAT2)") (class "Default")
      (node (ref "RN3") (pin "1") (pinfunction "1_1") (pintype "passive"))
      (node (ref "USD") (pin "1") (pinfunction "DAT2_1") (pintype "bidirectional"))
    )
    (net (code "55") (name "Net-(USD-SCLK)") (class "Default")
      (node (ref "R33") (pin "2") (pinfunction "2_2") (pintype "passive"))
      (node (ref "USD") (pin "5") (pinfunction "SCLK_5") (pintype "bidirectional"))
    )
    (net (code "56") (name "PHY-PWR") (class "Default")
      (node (ref "ESP1") (pin "14") (pinfunction "GPIO12_14") (pintype "bidirectional"))
    )
    (net (code "57") (name "PWR-SNS") (class "Default")
      (node (ref "ESP1") (pin "5") (pinfunction "SENSOR_VN_5") (pintype "bidirectional"))
      (node (ref "R43") (pin "2") (pinfunction "2_2") (pintype "passive"))
      (node (ref "R44") (pin "1") (pinfunction "1_1") (pintype "passive"))
    )
    (net (code "58") (name "SD-VCC") (class "Default")
      (node (ref "C15") (pin "1") (pinfunction "1_1") (pintype "passive"))
      (node (ref "C16") (pin "1") (pinfunction "1_1") (pintype "passive"))
      (node (ref "L2") (pin "2") (pinfunction "2_2") (pintype "passive"))
      (node (ref "USD") (pin "4") (pinfunction "VCC_4") (pintype "power_in"))
    )
    (net (code "59") (name "SUP-12V0") (class "Default")
      (node (ref "12V") (pin "1") (pinfunction "1_1") (pintype "passive"))
      (node (ref "C18") (pin "+") (pinfunction "+_+") (pintype "passive"))
      (node (ref "C20") (pin "1") (pinfunction "1_1") (pintype "passive"))
      (node (ref "C22") (pin "1") (pinfunction "1_1") (pintype "passive"))
      (node (ref "D1") (pin "C") (pinfunction "C_C") (pintype "passive"))
      (node (ref "DC1") (pin "1") (pinfunction "+VIN_1") (pintype "passive"))
    )
    (net (code "60") (name "SUP-GND") (class "Default")
      (node (ref "12V") (pin "2") (pinfunction "1_2") (pintype "passive"))
      (node (ref "C18") (pin "-") (pinfunction "-_-") (pintype "passive"))
      (node (ref "C21") (pin "1") (pinfunction "1_1") (pintype "passive"))
      (node (ref "C22") (pin "2") (pinfunction "2_2") (pintype "passive"))
      (node (ref "D1") (pin "A") (pinfunction "A_A") (pintype "passive"))
      (node (ref "DC1") (pin "2") (pinfunction "-VIN_2") (pintype "passive"))
    )
    (net (code "61") (name "UEXT-RX") (class "Default")
      (node (ref "ESP1") (pin "8") (pinfunction "GPIO32_8") (pintype "bidirectional"))
      (node (ref "RN4") (pin "4") (pinfunction "4_4") (pintype "passive"))
      (node (ref "UEXT") (pin "4") (pinfunction "4_4") (pintype "passive"))
    )
    (net (code "62") (name "UEXT-TX") (class "Default")
      (node (ref "ESP1") (pin "9") (pinfunction "GPIO33_9") (pintype "bidirectional"))
      (node (ref "UEXT") (pin "3") (pinfunction "3_3") (pintype "passive"))
    )
    (net (code "63") (name "USB-D_N") (class "Default")
      (node (ref "IC6") (pin "2") (pinfunction "D-_2") (pintype "bidirectional"))
      (node (ref "U2") (pin "1") (pinfunction "IO1_1") (pintype "passive"))
      (node (ref "USB") (pin "D-") (pinfunction "D-_D-") (pintype "bidirectional"))
    )
    (net (code "64") (name "USB-D_P") (class "Default")
      (node (ref "IC6") (pin "1") (pinfunction "D+_1") (pintype "bidirectional"))
      (node (ref "U2") (pin "5") (pinfunction "IO4_5") (pintype "passive"))
      (node (ref "USB") (pin "D+") (pinfunction "D+_D+") (pintype "bidirectional"))
    )
    (net (code "65") (name "USB-VBUS") (class "Default")
      (node (ref "Q7") (pin "3") (pinfunction "D_3") (pintype "passive"))
      (node (ref "USB") (pin "VBUS") (pinfunction "VCC_VBUS") (pintype "bidirectional"))
    )
    (net (code "66") (name "unconnected-(ESP1-GPIO35-Pad7)") (class "Default")
      (node (ref "ESP1") (pin "7") (pinfunction "GPIO35_7") (pintype "bidirectional"))
    )
    (net (code "67") (name "unconnected-(RST-Pad1)") (class "Default")
      (node (ref "RST") (pin "1") (pinfunction "1_1") (pintype "passive"))
    )
    (net (code "68") (name "unconnected-(USB-PadID)") (class "Default")
      (node (ref "USB") (pin "ID") (pinfunction "ID_ID") (pintype "bidirectional"))
    )
    (net (code "69") (name "unconnected-(USD-CDET-Pad9)") (class "Default")
      (node (ref "USD") (pin "9") (pinfunction "CDET_9") (pintype "passive"))
    )
  )
)
